# VoltCalBoard.net
KiCad netlist of a schematic drawn in EAGLE
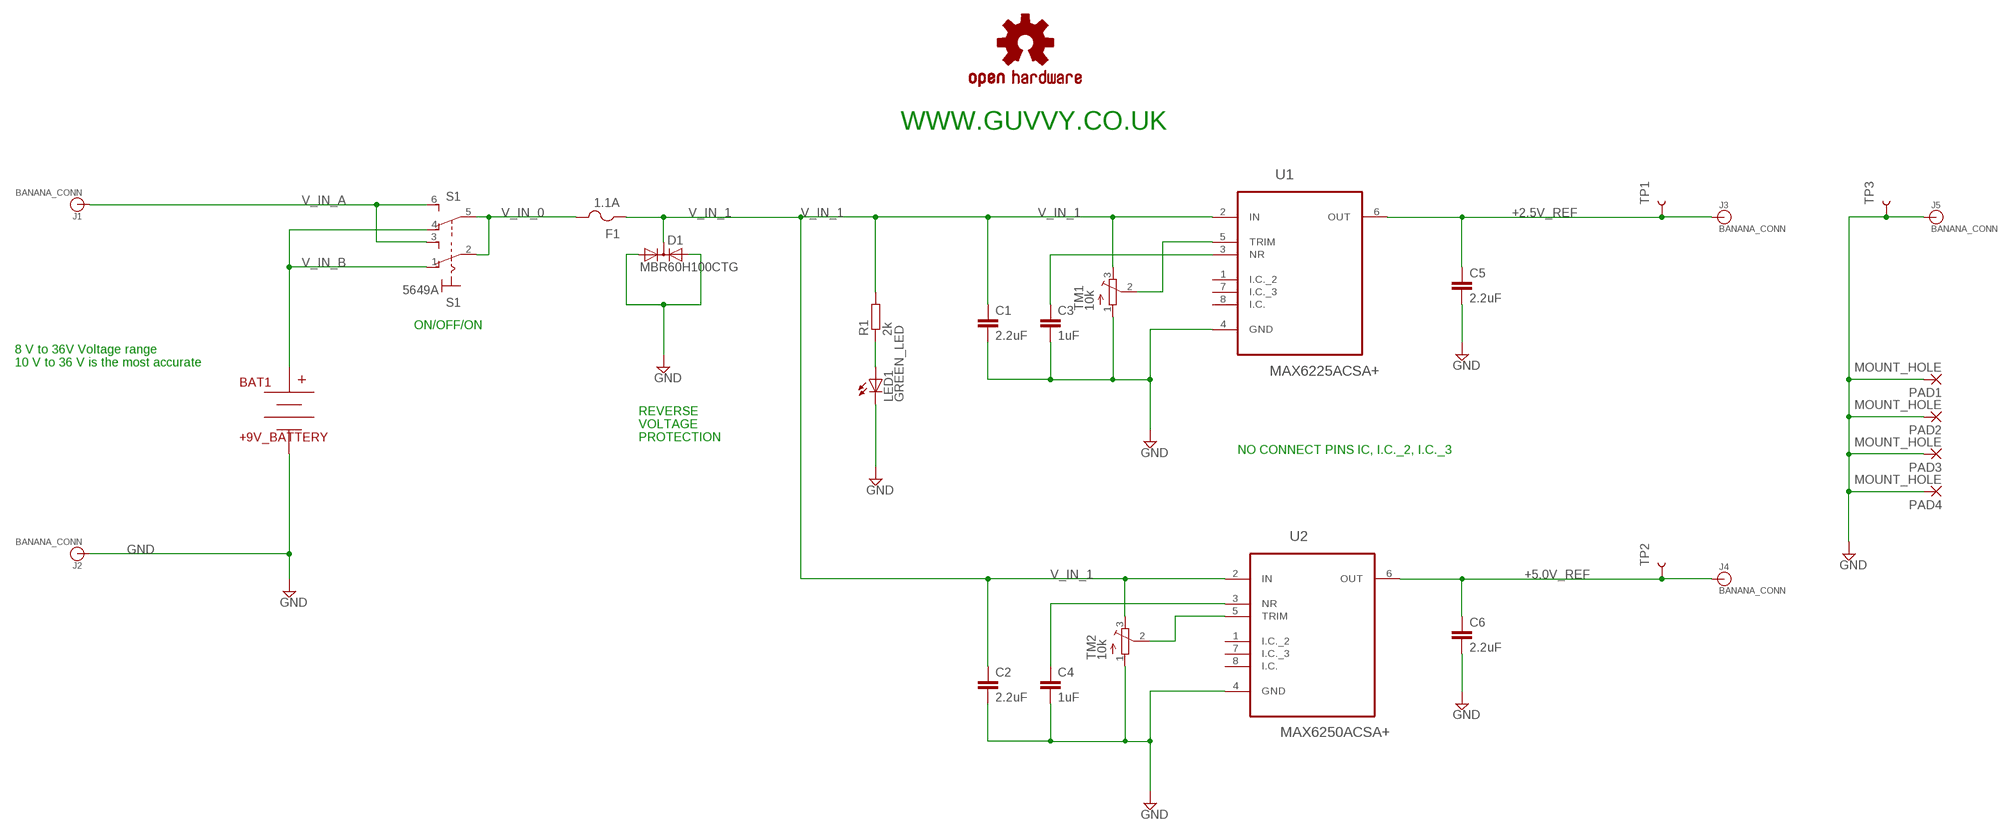
[diagram p0: schematic, sheet 1]

(export (version "E")
  (design (tool "Eeschema 10.0.6"))
  (components
    (comp (ref "BAT1")
      (value "+9V_BATTERY")
      (footprint "eagle-import:BC9VPC")
      (libsource (lib "eagle-import") (part "BC9VPC"))
    )
    (comp (ref "C1")
      (value "2.2uF")
      (footprint "eagle-import:C0805")
      (libsource (lib "eagle-import") (part "C-EUC0805"))
    )
    (comp (ref "C2")
      (value "2.2uF")
      (footprint "eagle-import:C0805")
      (libsource (lib "eagle-import") (part "C-EUC0805"))
    )
    (comp (ref "C3")
      (value "1uF")
      (footprint "eagle-import:C0805")
      (libsource (lib "eagle-import") (part "C-EUC0805"))
    )
    (comp (ref "C4")
      (value "1uF")
      (footprint "eagle-import:C0805")
      (libsource (lib "eagle-import") (part "C-EUC0805"))
    )
    (comp (ref "C5")
      (value "2.2uF")
      (footprint "eagle-import:C0805")
      (libsource (lib "eagle-import") (part "C-EUC0805"))
    )
    (comp (ref "C6")
      (value "2.2uF")
      (footprint "eagle-import:C0805")
      (libsource (lib "eagle-import") (part "C-EUC0805"))
    )
    (comp (ref "D1")
      (value "MBR60H100CTG")
      (footprint "eagle-import:TO220ABS")
      (fields (field (name "MF") "ON SEMICONDUCTOR"))
      (libsource (lib "eagle-import") (part "DIODE-2AC|CATO220V"))
    )
    (comp (ref "F1")
      (value "1.1A")
      (footprint "eagle-import:1812")
      (fields (field (name "MF") "TE CONNECTIVITY / RAYCHEM") (field (name "MPN") "MINISMDC110F/24-2"))
      (libsource (lib "eagle-import") (part "PTCFUSE-1812"))
    )
    (comp (ref "J1")
      (value "BANANA_CONN")
      (footprint "eagle-import:BANANA_CONN")
      (libsource (lib "eagle-import") (part "BANANA_CONN"))
    )
    (comp (ref "J2")
      (value "BANANA_CONN")
      (footprint "eagle-import:BANANA_CONN")
      (libsource (lib "eagle-import") (part "BANANA_CONN"))
    )
    (comp (ref "J3")
      (value "BANANA_CONN")
      (footprint "eagle-import:BANANA_CONN")
      (libsource (lib "eagle-import") (part "BANANA_CONN"))
    )
    (comp (ref "J4")
      (value "BANANA_CONN")
      (footprint "eagle-import:BANANA_CONN")
      (libsource (lib "eagle-import") (part "BANANA_CONN"))
    )
    (comp (ref "J5")
      (value "BANANA_CONN")
      (footprint "eagle-import:BANANA_CONN")
      (libsource (lib "eagle-import") (part "BANANA_CONN"))
    )
    (comp (ref "LED1")
      (value "GREEN_LED")
      (footprint "eagle-import:P-LCC-2")
      (libsource (lib "eagle-import") (part "LEDP-LCC-2"))
    )
    (comp (ref "LOGO1")
      (value "OSHW-LOGOL")
      (footprint "eagle-import:OSHW-LOGO-L")
      (libsource (lib "eagle-import") (part "OSHW-LOGOL"))
    )
    (comp (ref "PAD1")
      (value "MOUNT_HOLE")
      (footprint "eagle-import:3,81_1,4")
      (libsource (lib "eagle-import") (part "3,81/1,4"))
    )
    (comp (ref "PAD2")
      (value "MOUNT_HOLE")
      (footprint "eagle-import:3,81_1,4")
      (libsource (lib "eagle-import") (part "3,81/1,4"))
    )
    (comp (ref "PAD3")
      (value "MOUNT_HOLE")
      (footprint "eagle-import:3,81_1,4")
      (libsource (lib "eagle-import") (part "3,81/1,4"))
    )
    (comp (ref "PAD4")
      (value "MOUNT_HOLE")
      (footprint "eagle-import:3,81_1,4")
      (libsource (lib "eagle-import") (part "3,81/1,4"))
    )
    (comp (ref "R1")
      (value "2k")
      (footprint "eagle-import:R0805")
      (libsource (lib "eagle-import") (part "R-EU_R0805"))
    )
    (comp (ref "S1")
      (value "5649A")
      (footprint "eagle-import:320-938")
      (fields (field (name "MF") "APEM") (field (name "MPN") "5649A") (field (name "OC_FARNELL") "1082316"))
      (libsource (lib "eagle-import") (part "320-938"))
    )
    (comp (ref "TM1")
      (value "10k")
      (footprint "eagle-import:TC33X")
      (libsource (lib "eagle-import") (part "TRIMPOTTC33X"))
    )
    (comp (ref "TM2")
      (value "10k")
      (footprint "eagle-import:TC33X")
      (libsource (lib "eagle-import") (part "TRIMPOTTC33X"))
    )
    (comp (ref "TP1")
      (value "TP_1MM_TH\"")
      (footprint "eagle-import:TP_1MM_TH")
      (libsource (lib "eagle-import") (part "TP_1MM_TH{dblquote}"))
    )
    (comp (ref "TP2")
      (value "TP_1MM_TH\"")
      (footprint "eagle-import:TP_1MM_TH")
      (libsource (lib "eagle-import") (part "TP_1MM_TH{dblquote}"))
    )
    (comp (ref "TP3")
      (value "TP_1MM_TH\"")
      (footprint "eagle-import:TP_1MM_TH")
      (libsource (lib "eagle-import") (part "TP_1MM_TH{dblquote}"))
    )
    (comp (ref "U1")
      (value "MAX6225ACSA+")
      (footprint "eagle-import:SOIC127P600X175-8N")
      (fields (field (name "MF") "MAXIM INTEGRATED PRODUCTS") (field (name "OC_FARNELL") "2113189"))
      (libsource (lib "eagle-import") (part "MAX6225ACSA+"))
    )
    (comp (ref "U2")
      (value "MAX6250ACSA+")
      (footprint "eagle-import:SOIC127P600X175-8N")
      (fields (field (name "MF") "MAXIM INTEGRATED PRODUCTS"))
      (libsource (lib "eagle-import") (part "MAX6250ACSA+"))
    )
  )
  (nets
    (net (code "1") (name "/+2.5V_REF") (class "Default")
      (node (ref "C5") (pin "1") (pinfunction "1_1") (pintype "passive"))
      (node (ref "J3") (pin "P$1") (pinfunction "1_P$1") (pintype "passive"))
      (node (ref "TP1") (pin "P$1") (pinfunction "1_P$1") (pintype "bidirectional"))
      (node (ref "U1") (pin "6") (pinfunction "OUT_6") (pintype "output"))
    )
    (net (code "2") (name "/+5.0V_REF") (class "Default")
      (node (ref "C6") (pin "1") (pinfunction "1_1") (pintype "passive"))
      (node (ref "J4") (pin "P$1") (pinfunction "1_P$1") (pintype "passive"))
      (node (ref "TP2") (pin "P$1") (pinfunction "1_P$1") (pintype "bidirectional"))
      (node (ref "U2") (pin "6") (pinfunction "OUT_6") (pintype "output"))
    )
    (net (code "3") (name "/V_IN_0") (class "Default")
      (node (ref "F1") (pin "2") (pinfunction "2_2") (pintype "passive"))
      (node (ref "S1") (pin "2") (pinfunction "P_2") (pintype "passive"))
      (node (ref "S1") (pin "5") (pinfunction "P_5") (pintype "passive"))
    )
    (net (code "4") (name "/V_IN_1") (class "Default")
      (node (ref "C1") (pin "1") (pinfunction "1_1") (pintype "passive"))
      (node (ref "C2") (pin "1") (pinfunction "1_1") (pintype "passive"))
      (node (ref "D1") (pin "C") (pinfunction "C_C") (pintype "passive"))
      (node (ref "F1") (pin "1") (pinfunction "1_1") (pintype "passive"))
      (node (ref "R1") (pin "2") (pinfunction "2_2") (pintype "passive"))
      (node (ref "TM1") (pin "3") (pinfunction "E_3") (pintype "passive"))
      (node (ref "TM2") (pin "3") (pinfunction "E_3") (pintype "passive"))
      (node (ref "U1") (pin "2") (pinfunction "IN_2") (pintype "input"))
      (node (ref "U2") (pin "2") (pinfunction "IN_2") (pintype "power_in"))
    )
    (net (code "5") (name "/V_IN_A") (class "Default")
      (node (ref "J1") (pin "P$1") (pinfunction "1_P$1") (pintype "passive"))
      (node (ref "S1") (pin "3") (pinfunction "S_3") (pintype "passive"))
      (node (ref "S1") (pin "6") (pinfunction "S_6") (pintype "passive"))
    )
    (net (code "6") (name "/V_IN_B") (class "Default")
      (node (ref "BAT1") (pin "V+") (pinfunction "V+_V+") (pintype "bidirectional"))
      (node (ref "S1") (pin "1") (pinfunction "O_1") (pintype "passive"))
      (node (ref "S1") (pin "4") (pinfunction "O_4") (pintype "passive"))
    )
    (net (code "7") (name "GND") (class "Default")
      (node (ref "BAT1") (pin "V-") (pinfunction "V-_V-") (pintype "bidirectional"))
      (node (ref "C1") (pin "2") (pinfunction "2_2") (pintype "passive"))
      (node (ref "C2") (pin "2") (pinfunction "2_2") (pintype "passive"))
      (node (ref "C3") (pin "2") (pinfunction "2_2") (pintype "passive"))
      (node (ref "C4") (pin "2") (pinfunction "2_2") (pintype "passive"))
      (node (ref "C5") (pin "2") (pinfunction "2_2") (pintype "passive"))
      (node (ref "C6") (pin "2") (pinfunction "2_2") (pintype "passive"))
      (node (ref "D1") (pin "A1") (pinfunction "A1_A1") (pintype "passive"))
      (node (ref "D1") (pin "A2") (pinfunction "A2_A2") (pintype "passive"))
      (node (ref "J2") (pin "P$1") (pinfunction "1_P$1") (pintype "passive"))
      (node (ref "J5") (pin "P$1") (pinfunction "1_P$1") (pintype "passive"))
      (node (ref "LED1") (pin "C") (pinfunction "C_C") (pintype "passive"))
      (node (ref "PAD1") (pin "1") (pinfunction "P_1") (pintype "passive"))
      (node (ref "PAD2") (pin "1") (pinfunction "P_1") (pintype "passive"))
      (node (ref "PAD3") (pin "1") (pinfunction "P_1") (pintype "passive"))
      (node (ref "PAD4") (pin "1") (pinfunction "P_1") (pintype "passive"))
      (node (ref "TM1") (pin "1") (pinfunction "A_1") (pintype "passive"))
      (node (ref "TM2") (pin "1") (pinfunction "A_1") (pintype "passive"))
      (node (ref "TP3") (pin "P$1") (pinfunction "1_P$1") (pintype "bidirectional"))
      (node (ref "U1") (pin "4") (pinfunction "GND_4") (pintype "passive"))
      (node (ref "U2") (pin "4") (pinfunction "GND_4") (pintype "passive"))
    )
    (net (code "8") (name "Net-(LED1-PadA)") (class "Default")
      (node (ref "LED1") (pin "A") (pinfunction "A_A") (pintype "passive"))
      (node (ref "R1") (pin "1") (pinfunction "1_1") (pintype "passive"))
    )
    (net (code "9") (name "Net-(TM1-S)") (class "Default")
      (node (ref "TM1") (pin "2") (pinfunction "S_2") (pintype "passive"))
      (node (ref "U1") (pin "5") (pinfunction "TRIM_5") (pintype "input"))
    )
    (net (code "10") (name "Net-(TM2-S)") (class "Default")
      (node (ref "TM2") (pin "2") (pinfunction "S_2") (pintype "passive"))
      (node (ref "U2") (pin "5") (pinfunction "TRIM_5") (pintype "input"))
    )
    (net (code "11") (name "Net-(U1-NR)") (class "Default")
      (node (ref "C3") (pin "1") (pinfunction "1_1") (pintype "passive"))
      (node (ref "U1") (pin "3") (pinfunction "NR_3") (pintype "input"))
    )
    (net (code "12") (name "Net-(U2-NR)") (class "Default")
      (node (ref "C4") (pin "1") (pinfunction "1_1") (pintype "passive"))
      (node (ref "U2") (pin "3") (pinfunction "NR_3") (pintype "input"))
    )
    (net (code "13") (name "unconnected-(U1-I.C.-Pad8)") (class "Default")
      (node (ref "U1") (pin "8") (pinfunction "I.C._8") (pintype "passive"))
    )
    (net (code "14") (name "unconnected-(U1-I.C._2-Pad1)") (class "Default")
      (node (ref "U1") (pin "1") (pinfunction "I.C._2_1") (pintype "passive"))
    )
    (net (code "15") (name "unconnected-(U1-I.C._3-Pad7)") (class "Default")
      (node (ref "U1") (pin "7") (pinfunction "I.C._3_7") (pintype "passive"))
    )
    (net (code "16") (name "unconnected-(U2-I.C.-Pad8)") (class "Default")
      (node (ref "U2") (pin "8") (pinfunction "I.C._8") (pintype "passive"))
    )
    (net (code "17") (name "unconnected-(U2-I.C._2-Pad1)") (class "Default")
      (node (ref "U2") (pin "1") (pinfunction "I.C._2_1") (pintype "passive"))
    )
    (net (code "18") (name "unconnected-(U2-I.C._3-Pad7)") (class "Default")
      (node (ref "U2") (pin "7") (pinfunction "I.C._3_7") (pintype "passive"))
    )
  )
)
